# 130818_I_T_V_AriloRX_0_2.net
KiCad netlist of a schematic drawn in EAGLE
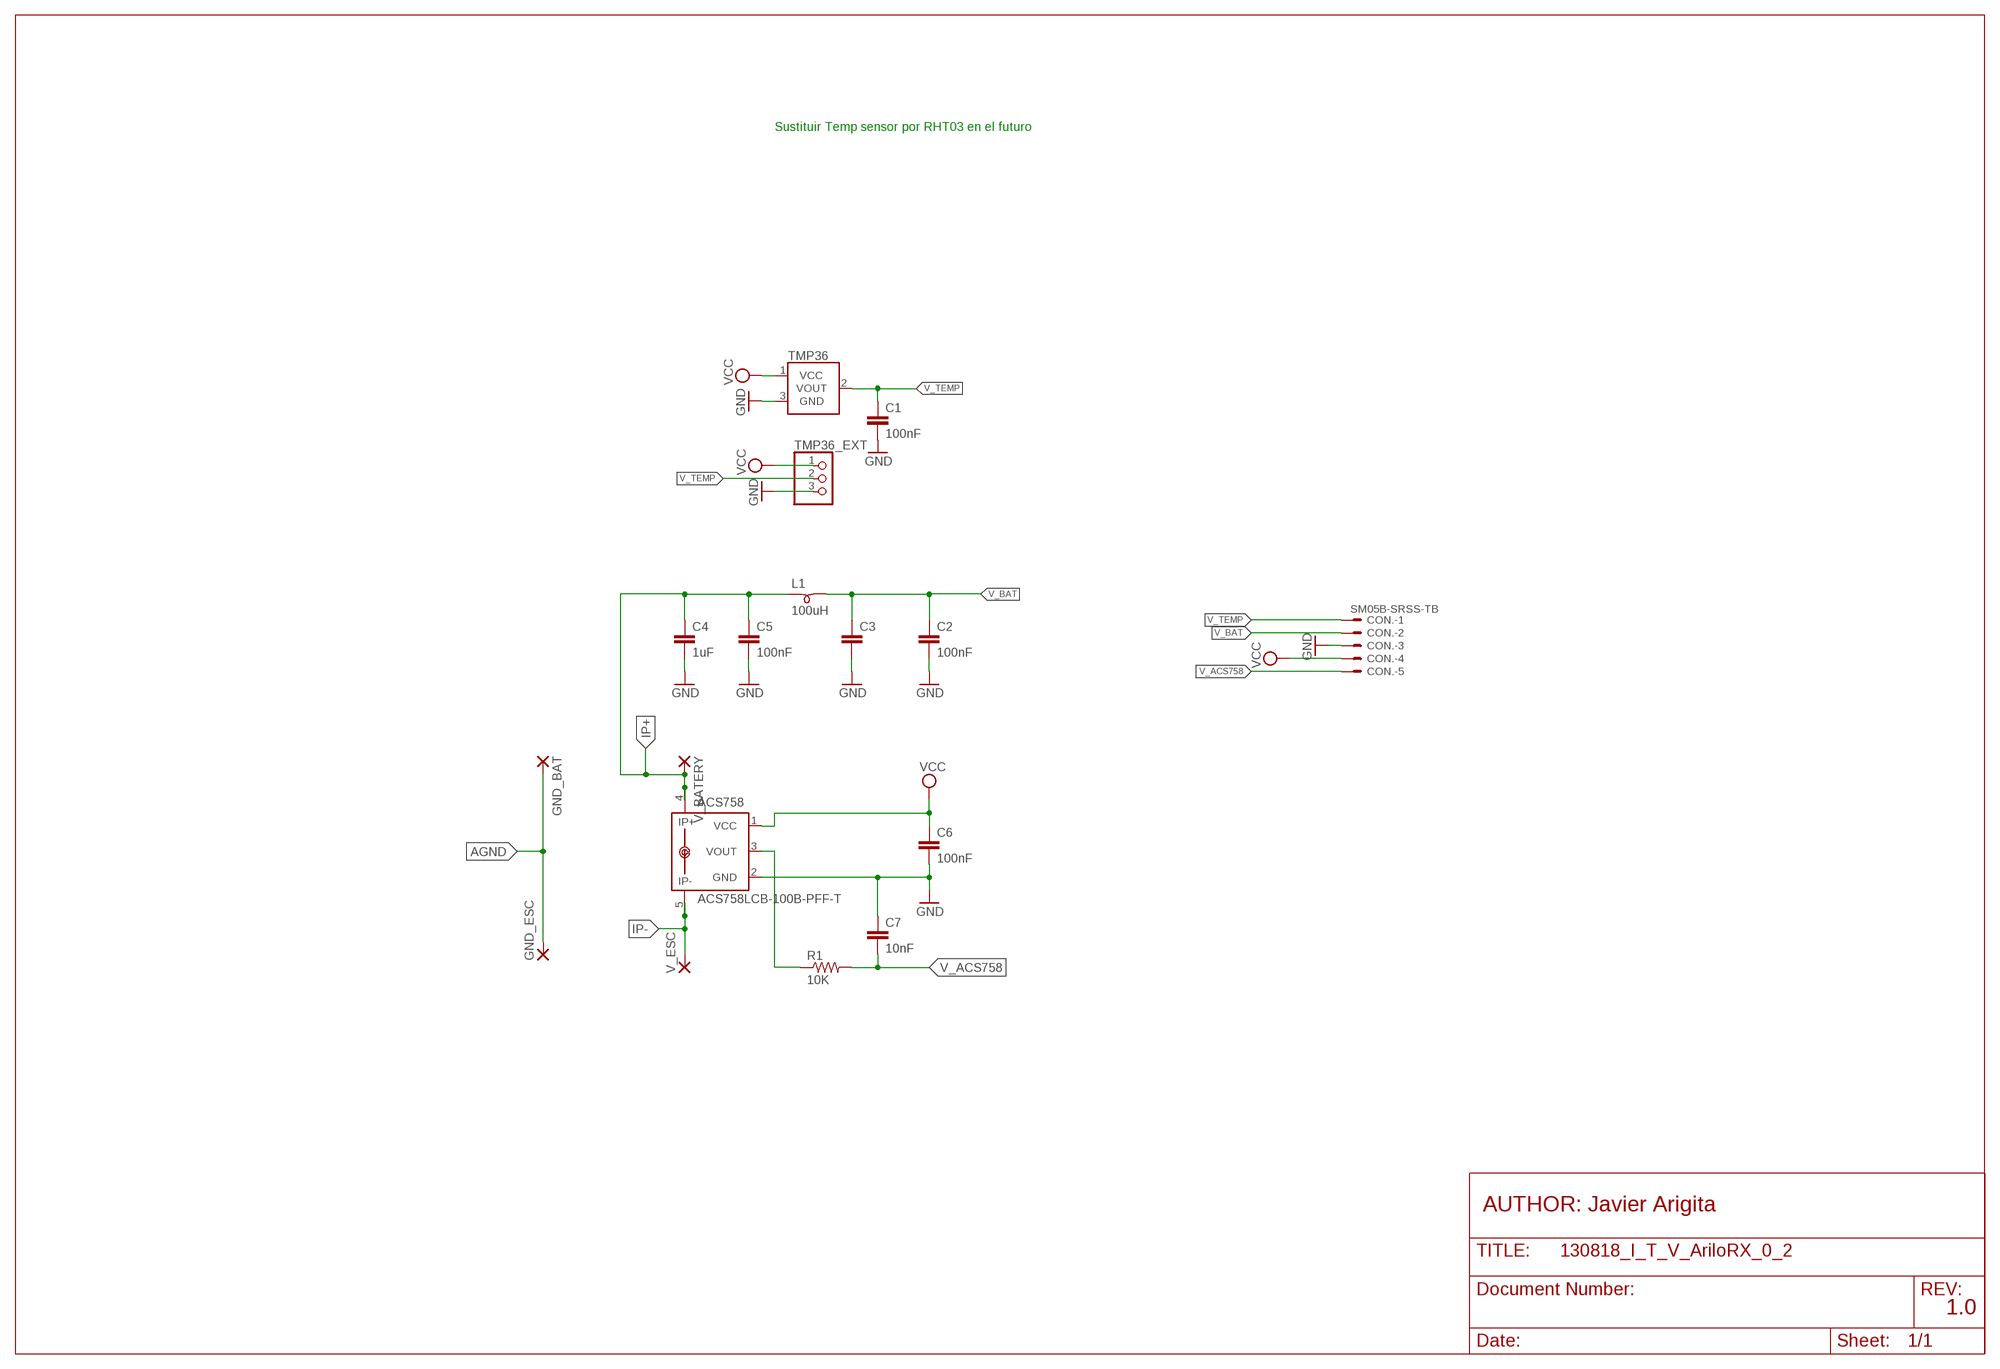
[diagram p0: schematic, sheet 1]

(export (version "E")
  (design (tool "Eeschema 10.0.6"))
  (components
    (comp (ref "ACS758")
      (value "ACS758LCB-100B-PFF-T")
      (footprint "eagle-import:CB-PFF")
      (libsource (lib "eagle-import") (part "ACS758LCB-100B-PFF-T"))
    )
    (comp (ref "C1")
      (value "100nF")
      (footprint "eagle-import:C0805")
      (libsource (lib "eagle-import") (part "C-EUC0805"))
    )
    (comp (ref "C2")
      (value "100nF")
      (footprint "eagle-import:C0805")
      (libsource (lib "eagle-import") (part "C-EUC0805"))
    )
    (comp (ref "C3")
      (value "C-EUC3216")
      (footprint "eagle-import:C3216")
      (libsource (lib "eagle-import") (part "C-EUC3216"))
    )
    (comp (ref "C4")
      (value "1uF")
      (footprint "eagle-import:C3216")
      (libsource (lib "eagle-import") (part "C-EUC3216"))
    )
    (comp (ref "C5")
      (value "100nF")
      (footprint "eagle-import:C0805")
      (libsource (lib "eagle-import") (part "C-EUC0805"))
    )
    (comp (ref "C6")
      (value "100nF")
      (footprint "eagle-import:C0805")
      (libsource (lib "eagle-import") (part "C-EUC0805"))
    )
    (comp (ref "C7")
      (value "10nF")
      (footprint "eagle-import:C0805")
      (libsource (lib "eagle-import") (part "C-EUC0805"))
    )
    (comp (ref "CON.")
      (value "SM05B-SRSS-TB")
      (footprint "eagle-import:SM05B-SRSS-TB")
      (libsource (lib "eagle-import") (part "?M05B-SRSS-TBS"))
    )
    (comp (ref "GND_BAT")
      (value "SMD5")
      (footprint "eagle-import:SMD2,54-5,08")
      (libsource (lib "eagle-import") (part "SMD5"))
    )
    (comp (ref "GND_ESC")
      (value "SMD5")
      (footprint "eagle-import:SMD2,54-5,08")
      (libsource (lib "eagle-import") (part "SMD5"))
    )
    (comp (ref "L1")
      (value "100uH")
      (footprint "eagle-import:SM-B5")
      (libsource (lib "eagle-import") (part "SM-B5"))
    )
    (comp (ref "R1")
      (value "10K")
      (footprint "eagle-import:R0805")
      (libsource (lib "eagle-import") (part "RESISTOR0805"))
    )
    (comp (ref "TMP36")
      (value "TMP36GT9")
      (footprint "eagle-import:TO-92")
      (libsource (lib "eagle-import") (part "TMP36GT9"))
    )
    (comp (ref "TMP36_EXT")
      (value "PINHD-1X3")
      (footprint "eagle-import:1X03")
      (libsource (lib "eagle-import") (part "PINHD-1X3"))
    )
    (comp (ref "V_BATERY")
      (value "SMD5")
      (footprint "eagle-import:SMD2,54-5,08")
      (libsource (lib "eagle-import") (part "SMD5"))
    )
    (comp (ref "V_ESC")
      (value "SMD5")
      (footprint "eagle-import:SMD2,54-5,08")
      (libsource (lib "eagle-import") (part "SMD5"))
    )
  )
  (nets
    (net (code "1") (name "AGND") (class "Default")
      (node (ref "GND_BAT") (pin "1") (pinfunction "P_1") (pintype "passive"))
      (node (ref "GND_ESC") (pin "1") (pinfunction "P_1") (pintype "passive"))
    )
    (net (code "2") (name "GND") (class "Default")
      (node (ref "ACS758") (pin "2") (pinfunction "GND_2") (pintype "power_in"))
      (node (ref "C1") (pin "2") (pinfunction "2_2") (pintype "passive"))
      (node (ref "C2") (pin "2") (pinfunction "2_2") (pintype "passive"))
      (node (ref "C3") (pin "2") (pinfunction "2_2") (pintype "passive"))
      (node (ref "C4") (pin "2") (pinfunction "2_2") (pintype "passive"))
      (node (ref "C5") (pin "2") (pinfunction "2_2") (pintype "passive"))
      (node (ref "C6") (pin "2") (pinfunction "2_2") (pintype "passive"))
      (node (ref "C7") (pin "1") (pinfunction "1_1") (pintype "passive"))
      (node (ref "CON.") (pin "3") (pinfunction "S_3") (pintype "passive"))
      (node (ref "TMP36") (pin "3") (pinfunction "GND_3") (pintype "bidirectional"))
      (node (ref "TMP36_EXT") (pin "3") (pinfunction "3_3") (pintype "passive"))
    )
    (net (code "3") (name "IP+") (class "Default")
      (node (ref "ACS758") (pin "4") (pinfunction "IP+_4") (pintype "passive"))
      (node (ref "ACS758") (pin "IP+1") (pinfunction "IP+1_IP+1") (pintype "input"))
      (node (ref "C4") (pin "1") (pinfunction "1_1") (pintype "passive"))
      (node (ref "C5") (pin "1") (pinfunction "1_1") (pintype "passive"))
      (node (ref "L1") (pin "1") (pinfunction "1_1") (pintype "passive"))
      (node (ref "V_BATERY") (pin "1") (pinfunction "P_1") (pintype "passive"))
    )
    (net (code "4") (name "IP-") (class "Default")
      (node (ref "ACS758") (pin "5") (pinfunction "IP-_5") (pintype "passive"))
      (node (ref "ACS758") (pin "IP-1") (pinfunction "IP-1_IP-1") (pintype "input"))
      (node (ref "V_ESC") (pin "1") (pinfunction "P_1") (pintype "passive"))
    )
    (net (code "5") (name "Net-(ACS758-VOUT)") (class "Default")
      (node (ref "ACS758") (pin "3") (pinfunction "VOUT_3") (pintype "output"))
      (node (ref "R1") (pin "1") (pinfunction "1_1") (pintype "passive"))
    )
    (net (code "6") (name "VCC") (class "Default")
      (node (ref "ACS758") (pin "1") (pinfunction "VCC_1") (pintype "power_in"))
      (node (ref "C6") (pin "1") (pinfunction "1_1") (pintype "passive"))
      (node (ref "CON.") (pin "4") (pinfunction "S_4") (pintype "passive"))
      (node (ref "TMP36") (pin "1") (pinfunction "VCC_1") (pintype "bidirectional"))
      (node (ref "TMP36_EXT") (pin "1") (pinfunction "1_1") (pintype "passive"))
    )
    (net (code "7") (name "V_ACS758") (class "Default")
      (node (ref "C7") (pin "2") (pinfunction "2_2") (pintype "passive"))
      (node (ref "CON.") (pin "5") (pinfunction "S_5") (pintype "passive"))
      (node (ref "R1") (pin "2") (pinfunction "2_2") (pintype "passive"))
    )
    (net (code "8") (name "V_BAT") (class "Default")
      (node (ref "C2") (pin "1") (pinfunction "1_1") (pintype "passive"))
      (node (ref "C3") (pin "1") (pinfunction "1_1") (pintype "passive"))
      (node (ref "CON.") (pin "2") (pinfunction "S_2") (pintype "passive"))
      (node (ref "L1") (pin "2") (pinfunction "2_2") (pintype "passive"))
    )
    (net (code "9") (name "V_TEMP") (class "Default")
      (node (ref "C1") (pin "1") (pinfunction "1_1") (pintype "passive"))
      (node (ref "CON.") (pin "1") (pinfunction "S_1") (pintype "passive"))
      (node (ref "TMP36") (pin "2") (pinfunction "VOUT_2") (pintype "bidirectional"))
      (node (ref "TMP36_EXT") (pin "2") (pinfunction "2_2") (pintype "passive"))
    )
  )
)
